# Pyros.net
KiCad netlist of a schematic drawn in Altium Designer
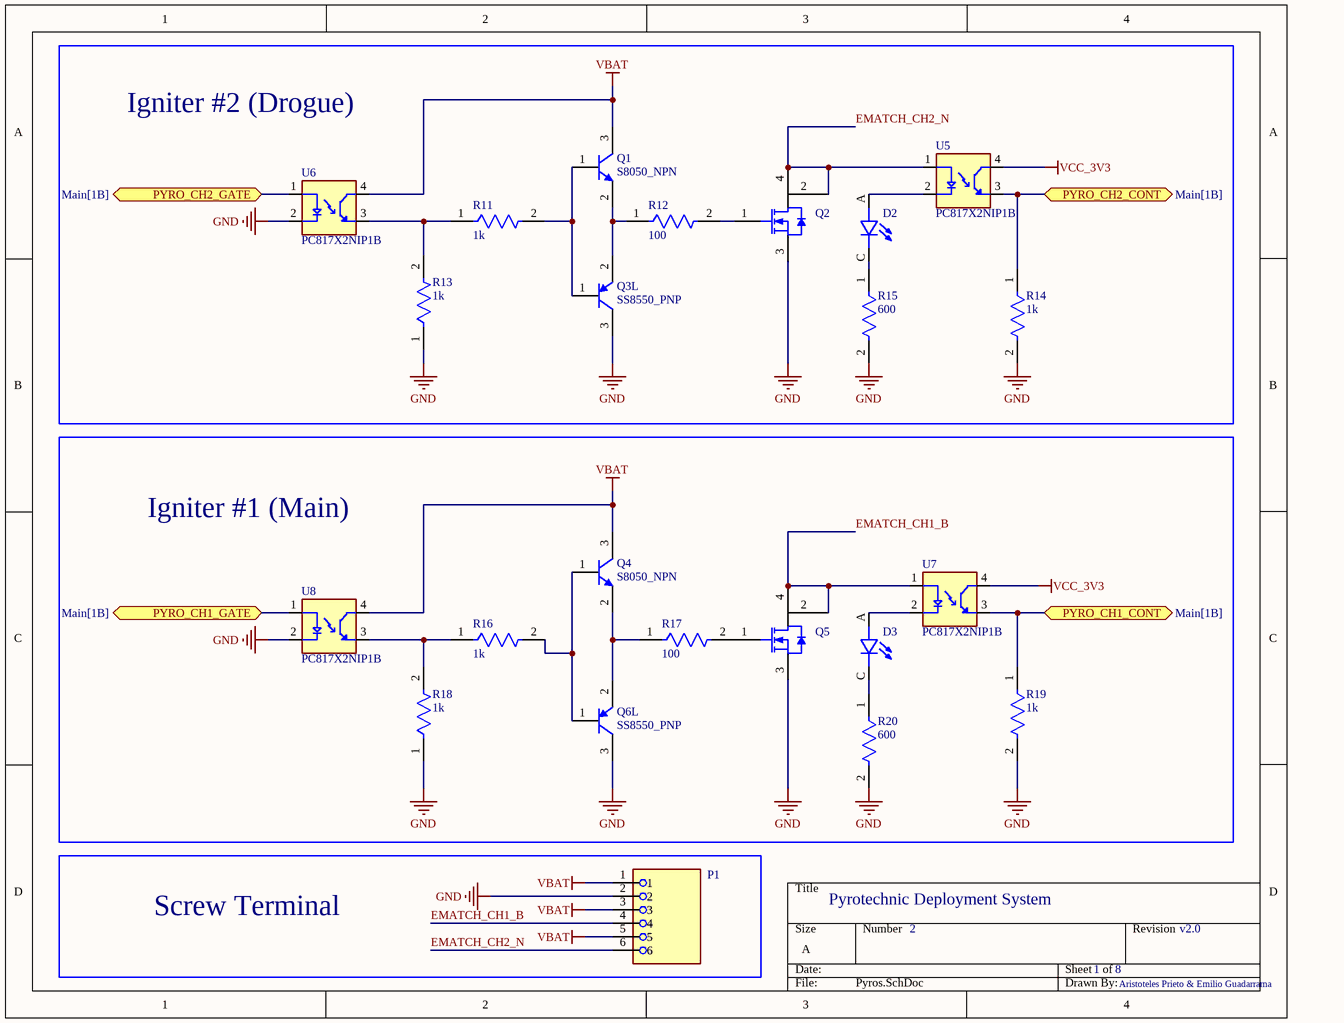
[diagram p0: Pyros.SchDoc]

(export (version "E")
  (design (tool "Eeschema 10.0.6"))
  (components
    (comp (ref "D2")
      (value "SML-LXT0805IW-TR")
      (footprint "LEDC2012X120N")
      (fields (field (name "MF") "Lumex Opto/Components"))
      (libsource (lib "LED_0805-SML-LXT0805IW-TR") (part "SML-LXT0805IW-TR"))
    )
    (comp (ref "D3")
      (value "SML-LXT0805IW-TR")
      (footprint "LEDC2012X120N")
      (fields (field (name "MF") "Lumex Opto/Components"))
      (libsource (lib "LED_0805-SML-LXT0805IW-TR") (part "SML-LXT0805IW-TR"))
    )
    (comp (ref "P1")
      (value "1729160")
      (footprint "PHOENIX_1729160")
      (fields (field (name "MF") "Phoenix Contact"))
      (libsource (lib "Terminal Screw 5.08mm (6 pin)") (part "1729160"))
    )
    (comp (ref "Q1")
      (value "S8050_NPN")
      (footprint "PCBComponent_1")
      (libsource (lib "NPN_8050") (part "Component_1"))
    )
    (comp (ref "Q2")
      (value "NCE6005AR_Mosfet_N")
      (footprint "PCBComponent_1")
      (libsource (lib "NCE6005AR_Mosfet_N") (part "NCE6005AR"))
    )
    (comp (ref "Q3")
      (value "SS8550_PNP")
      (footprint "PCBComponent_1")
      (libsource (lib "SS8550_PNP") (part "Component_1"))
    )
    (comp (ref "Q4")
      (value "S8050_NPN")
      (footprint "PCBComponent_1")
      (libsource (lib "NPN_8050") (part "Component_1"))
    )
    (comp (ref "Q5")
      (value "NCE6005AR_Mosfet_N")
      (footprint "PCBComponent_1")
      (libsource (lib "NCE6005AR_Mosfet_N") (part "NCE6005AR"))
    )
    (comp (ref "Q6")
      (value "SS8550_PNP")
      (footprint "PCBComponent_1")
      (libsource (lib "SS8550_PNP") (part "Component_1"))
    )
    (comp (ref "R11")
      (value "1k")
      (footprint "FP-MCT0603-IPC_A")
      (description "RES SMD 100 OHM 1% 1/8W 0603")
      (fields (field (name "TOLERANCE") "0.1%"))
      (libsource (lib "Altium Content Vault") (part "1029c3af85768c4190bb7ad29bc67b5"))
    )
    (comp (ref "R12")
      (value "100")
      (footprint "FP-MCT0603-IPC_A")
      (description "RES SMD 100 OHM 1% 1/8W 0603")
      (fields (field (name "TOLERANCE") "0.1%"))
      (libsource (lib "Altium Content Vault") (part "1029c3af85768c4190bb7ad29bc67b5"))
    )
    (comp (ref "R13")
      (value "1k")
      (footprint "FP-MCT0603-IPC_A")
      (description "RES SMD 100 OHM 1% 1/8W 0603")
      (fields (field (name "TOLERANCE") "0.1%"))
      (libsource (lib "Altium Content Vault") (part "1029c3af85768c4190bb7ad29bc67b5"))
    )
    (comp (ref "R14")
      (value "1k")
      (footprint "FP-MCT0603-IPC_A")
      (description "RES SMD 100 OHM 1% 1/8W 0603")
      (fields (field (name "TOLERANCE") "0.1%"))
      (libsource (lib "Altium Content Vault") (part "1029c3af85768c4190bb7ad29bc67b5"))
    )
    (comp (ref "R15")
      (value "600")
      (footprint "FP-MCT0603-IPC_A")
      (description "RES SMD 100 OHM 1% 1/8W 0603")
      (fields (field (name "TOLERANCE") "0.1%"))
      (libsource (lib "Altium Content Vault") (part "1029c3af85768c4190bb7ad29bc67b5"))
    )
    (comp (ref "R16")
      (value "1k")
      (footprint "FP-MCT0603-IPC_A")
      (description "RES SMD 100 OHM 1% 1/8W 0603")
      (fields (field (name "TOLERANCE") "0.1%"))
      (libsource (lib "Altium Content Vault") (part "1029c3af85768c4190bb7ad29bc67b5"))
    )
    (comp (ref "R17")
      (value "100")
      (footprint "FP-MCT0603-IPC_A")
      (description "RES SMD 100 OHM 1% 1/8W 0603")
      (fields (field (name "TOLERANCE") "0.1%"))
      (libsource (lib "Altium Content Vault") (part "1029c3af85768c4190bb7ad29bc67b5"))
    )
    (comp (ref "R18")
      (value "1k")
      (footprint "FP-MCT0603-IPC_A")
      (description "RES SMD 100 OHM 1% 1/8W 0603")
      (fields (field (name "TOLERANCE") "0.1%"))
      (libsource (lib "Altium Content Vault") (part "1029c3af85768c4190bb7ad29bc67b5"))
    )
    (comp (ref "R19")
      (value "1k")
      (footprint "FP-MCT0603-IPC_A")
      (description "RES SMD 100 OHM 1% 1/8W 0603")
      (fields (field (name "TOLERANCE") "0.1%"))
      (libsource (lib "Altium Content Vault") (part "1029c3af85768c4190bb7ad29bc67b5"))
    )
    (comp (ref "R20")
      (value "600")
      (footprint "FP-MCT0603-IPC_A")
      (description "RES SMD 100 OHM 1% 1/8W 0603")
      (fields (field (name "TOLERANCE") "0.1%"))
      (libsource (lib "Altium Content Vault") (part "1029c3af85768c4190bb7ad29bc67b5"))
    )
    (comp (ref "U5")
      (value "PC817X2NIP1B")
      (footprint "SOIC254P960X420-4N")
      (description "Optocoupler DC-IN 1-CH Transistor DC-OUT 4-Pin DIP SMD T/R")
      (fields (field (name "MF") "Sharp Microelectronics"))
      (libsource (lib "Optoisolator-PC817X2NIP1B") (part "PC817X2NIP1B"))
    )
    (comp (ref "U6")
      (value "PC817X2NIP1B")
      (footprint "SOIC254P960X420-4N")
      (description "Optocoupler DC-IN 1-CH Transistor DC-OUT 4-Pin DIP SMD T/R")
      (fields (field (name "MF") "Sharp Microelectronics"))
      (libsource (lib "Optoisolator-PC817X2NIP1B") (part "PC817X2NIP1B"))
    )
    (comp (ref "U7")
      (value "PC817X2NIP1B")
      (footprint "SOIC254P960X420-4N")
      (description "Optocoupler DC-IN 1-CH Transistor DC-OUT 4-Pin DIP SMD T/R")
      (fields (field (name "MF") "Sharp Microelectronics"))
      (libsource (lib "Optoisolator-PC817X2NIP1B") (part "PC817X2NIP1B"))
    )
    (comp (ref "U8")
      (value "PC817X2NIP1B")
      (footprint "SOIC254P960X420-4N")
      (description "Optocoupler DC-IN 1-CH Transistor DC-OUT 4-Pin DIP SMD T/R")
      (fields (field (name "MF") "Sharp Microelectronics"))
      (libsource (lib "Optoisolator-PC817X2NIP1B") (part "PC817X2NIP1B"))
    )
  )
  (nets
    (net (code "1") (name "/EMATCH_CH1_B") (class "Default")
      (node (ref "P1") (pin "4") (pinfunction "4_4") (pintype "passive"))
      (node (ref "Q5") (pin "2") (pinfunction "D_2") (pintype "passive"))
      (node (ref "Q5") (pin "4") (pinfunction "D_4") (pintype "passive"))
      (node (ref "U7") (pin "1") (pinfunction "A_1") (pintype "passive"))
    )
    (net (code "2") (name "/EMATCH_CH2_N") (class "Default")
      (node (ref "P1") (pin "6") (pinfunction "6_6") (pintype "passive"))
      (node (ref "Q2") (pin "2") (pinfunction "D_2") (pintype "passive"))
      (node (ref "Q2") (pin "4") (pinfunction "D_4") (pintype "passive"))
      (node (ref "U5") (pin "1") (pinfunction "A_1") (pintype "passive"))
    )
    (net (code "3") (name "/PYRO_CH1_CONT") (class "Default")
      (node (ref "R19") (pin "1") (pinfunction "1_1") (pintype "passive"))
      (node (ref "U7") (pin "3") (pinfunction "ET_3") (pintype "passive"))
    )
    (net (code "4") (name "/PYRO_CH1_GATE") (class "Default")
      (node (ref "U8") (pin "1") (pinfunction "A_1") (pintype "passive"))
    )
    (net (code "5") (name "/PYRO_CH2_CONT") (class "Default")
      (node (ref "R14") (pin "1") (pinfunction "1_1") (pintype "passive"))
      (node (ref "U5") (pin "3") (pinfunction "ET_3") (pintype "passive"))
    )
    (net (code "6") (name "/PYRO_CH2_GATE") (class "Default")
      (node (ref "U6") (pin "1") (pinfunction "A_1") (pintype "passive"))
    )
    (net (code "7") (name "GND") (class "Default")
      (node (ref "P1") (pin "2") (pinfunction "2_2") (pintype "passive"))
      (node (ref "Q2") (pin "3") (pinfunction "S_3") (pintype "passive"))
      (node (ref "Q3") (pin "3") (pinfunction "C_3") (pintype "passive"))
      (node (ref "Q5") (pin "3") (pinfunction "S_3") (pintype "passive"))
      (node (ref "Q6") (pin "3") (pinfunction "C_3") (pintype "passive"))
      (node (ref "R13") (pin "1") (pinfunction "1_1") (pintype "passive"))
      (node (ref "R14") (pin "2") (pinfunction "2_2") (pintype "passive"))
      (node (ref "R15") (pin "2") (pinfunction "2_2") (pintype "passive"))
      (node (ref "R18") (pin "1") (pinfunction "1_1") (pintype "passive"))
      (node (ref "R19") (pin "2") (pinfunction "2_2") (pintype "passive"))
      (node (ref "R20") (pin "2") (pinfunction "2_2") (pintype "passive"))
      (node (ref "U6") (pin "2") (pinfunction "C_2") (pintype "passive"))
      (node (ref "U8") (pin "2") (pinfunction "C_2") (pintype "passive"))
    )
    (net (code "8") (name "Net-(D2-PadC)") (class "Default")
      (node (ref "D2") (pin "C") (pinfunction "C_C") (pintype "passive"))
      (node (ref "R15") (pin "1") (pinfunction "1_1") (pintype "passive"))
    )
    (net (code "9") (name "Net-(D3-PadC)") (class "Default")
      (node (ref "D3") (pin "C") (pinfunction "C_C") (pintype "passive"))
      (node (ref "R20") (pin "1") (pinfunction "1_1") (pintype "passive"))
    )
    (net (code "10") (name "Net-(Q1-B)") (class "Default")
      (node (ref "Q1") (pin "1") (pinfunction "B_1") (pintype "passive"))
      (node (ref "Q3") (pin "1") (pinfunction "B_1") (pintype "passive"))
      (node (ref "R11") (pin "2") (pinfunction "2_2") (pintype "passive"))
    )
    (net (code "11") (name "Net-(Q1-E)") (class "Default")
      (node (ref "Q1") (pin "2") (pinfunction "E_2") (pintype "passive"))
      (node (ref "Q3") (pin "2") (pinfunction "E_2") (pintype "passive"))
      (node (ref "R12") (pin "1") (pinfunction "1_1") (pintype "passive"))
    )
    (net (code "12") (name "Net-(Q2-G)") (class "Default")
      (node (ref "Q2") (pin "1") (pinfunction "G_1") (pintype "passive"))
      (node (ref "R12") (pin "2") (pinfunction "2_2") (pintype "passive"))
    )
    (net (code "13") (name "Net-(Q4-B)") (class "Default")
      (node (ref "Q4") (pin "1") (pinfunction "B_1") (pintype "passive"))
      (node (ref "Q6") (pin "1") (pinfunction "B_1") (pintype "passive"))
      (node (ref "R16") (pin "2") (pinfunction "2_2") (pintype "passive"))
    )
    (net (code "14") (name "Net-(Q4-E)") (class "Default")
      (node (ref "Q4") (pin "2") (pinfunction "E_2") (pintype "passive"))
      (node (ref "Q6") (pin "2") (pinfunction "E_2") (pintype "passive"))
      (node (ref "R17") (pin "1") (pinfunction "1_1") (pintype "passive"))
    )
    (net (code "15") (name "Net-(Q5-G)") (class "Default")
      (node (ref "Q5") (pin "1") (pinfunction "G_1") (pintype "passive"))
      (node (ref "R17") (pin "2") (pinfunction "2_2") (pintype "passive"))
    )
    (net (code "16") (name "Net-(U5-C)") (class "Default")
      (node (ref "D2") (pin "A") (pinfunction "A_A") (pintype "passive"))
      (node (ref "U5") (pin "2") (pinfunction "C_2") (pintype "passive"))
    )
    (net (code "17") (name "Net-(U6-ET)") (class "Default")
      (node (ref "R11") (pin "1") (pinfunction "1_1") (pintype "passive"))
      (node (ref "R13") (pin "2") (pinfunction "2_2") (pintype "passive"))
      (node (ref "U6") (pin "3") (pinfunction "ET_3") (pintype "passive"))
    )
    (net (code "18") (name "Net-(U7-C)") (class "Default")
      (node (ref "D3") (pin "A") (pinfunction "A_A") (pintype "passive"))
      (node (ref "U7") (pin "2") (pinfunction "C_2") (pintype "passive"))
    )
    (net (code "19") (name "Net-(U8-ET)") (class "Default")
      (node (ref "R16") (pin "1") (pinfunction "1_1") (pintype "passive"))
      (node (ref "R18") (pin "2") (pinfunction "2_2") (pintype "passive"))
      (node (ref "U8") (pin "3") (pinfunction "ET_3") (pintype "passive"))
    )
    (net (code "20") (name "VBAT") (class "Default")
      (node (ref "P1") (pin "1") (pinfunction "1_1") (pintype "passive"))
      (node (ref "P1") (pin "3") (pinfunction "3_3") (pintype "passive"))
      (node (ref "P1") (pin "5") (pinfunction "5_5") (pintype "passive"))
      (node (ref "Q1") (pin "3") (pinfunction "C_3") (pintype "passive"))
      (node (ref "Q4") (pin "3") (pinfunction "C_3") (pintype "passive"))
      (node (ref "U6") (pin "4") (pinfunction "CT_4") (pintype "passive"))
      (node (ref "U8") (pin "4") (pinfunction "CT_4") (pintype "passive"))
    )
    (net (code "21") (name "VCC_3V3") (class "Default")
      (node (ref "U5") (pin "4") (pinfunction "CT_4") (pintype "passive"))
      (node (ref "U7") (pin "4") (pinfunction "CT_4") (pintype "passive"))
    )
  )
)
